# Un_AVR_V2_0.net
KiCad netlist of a schematic drawn in EAGLE
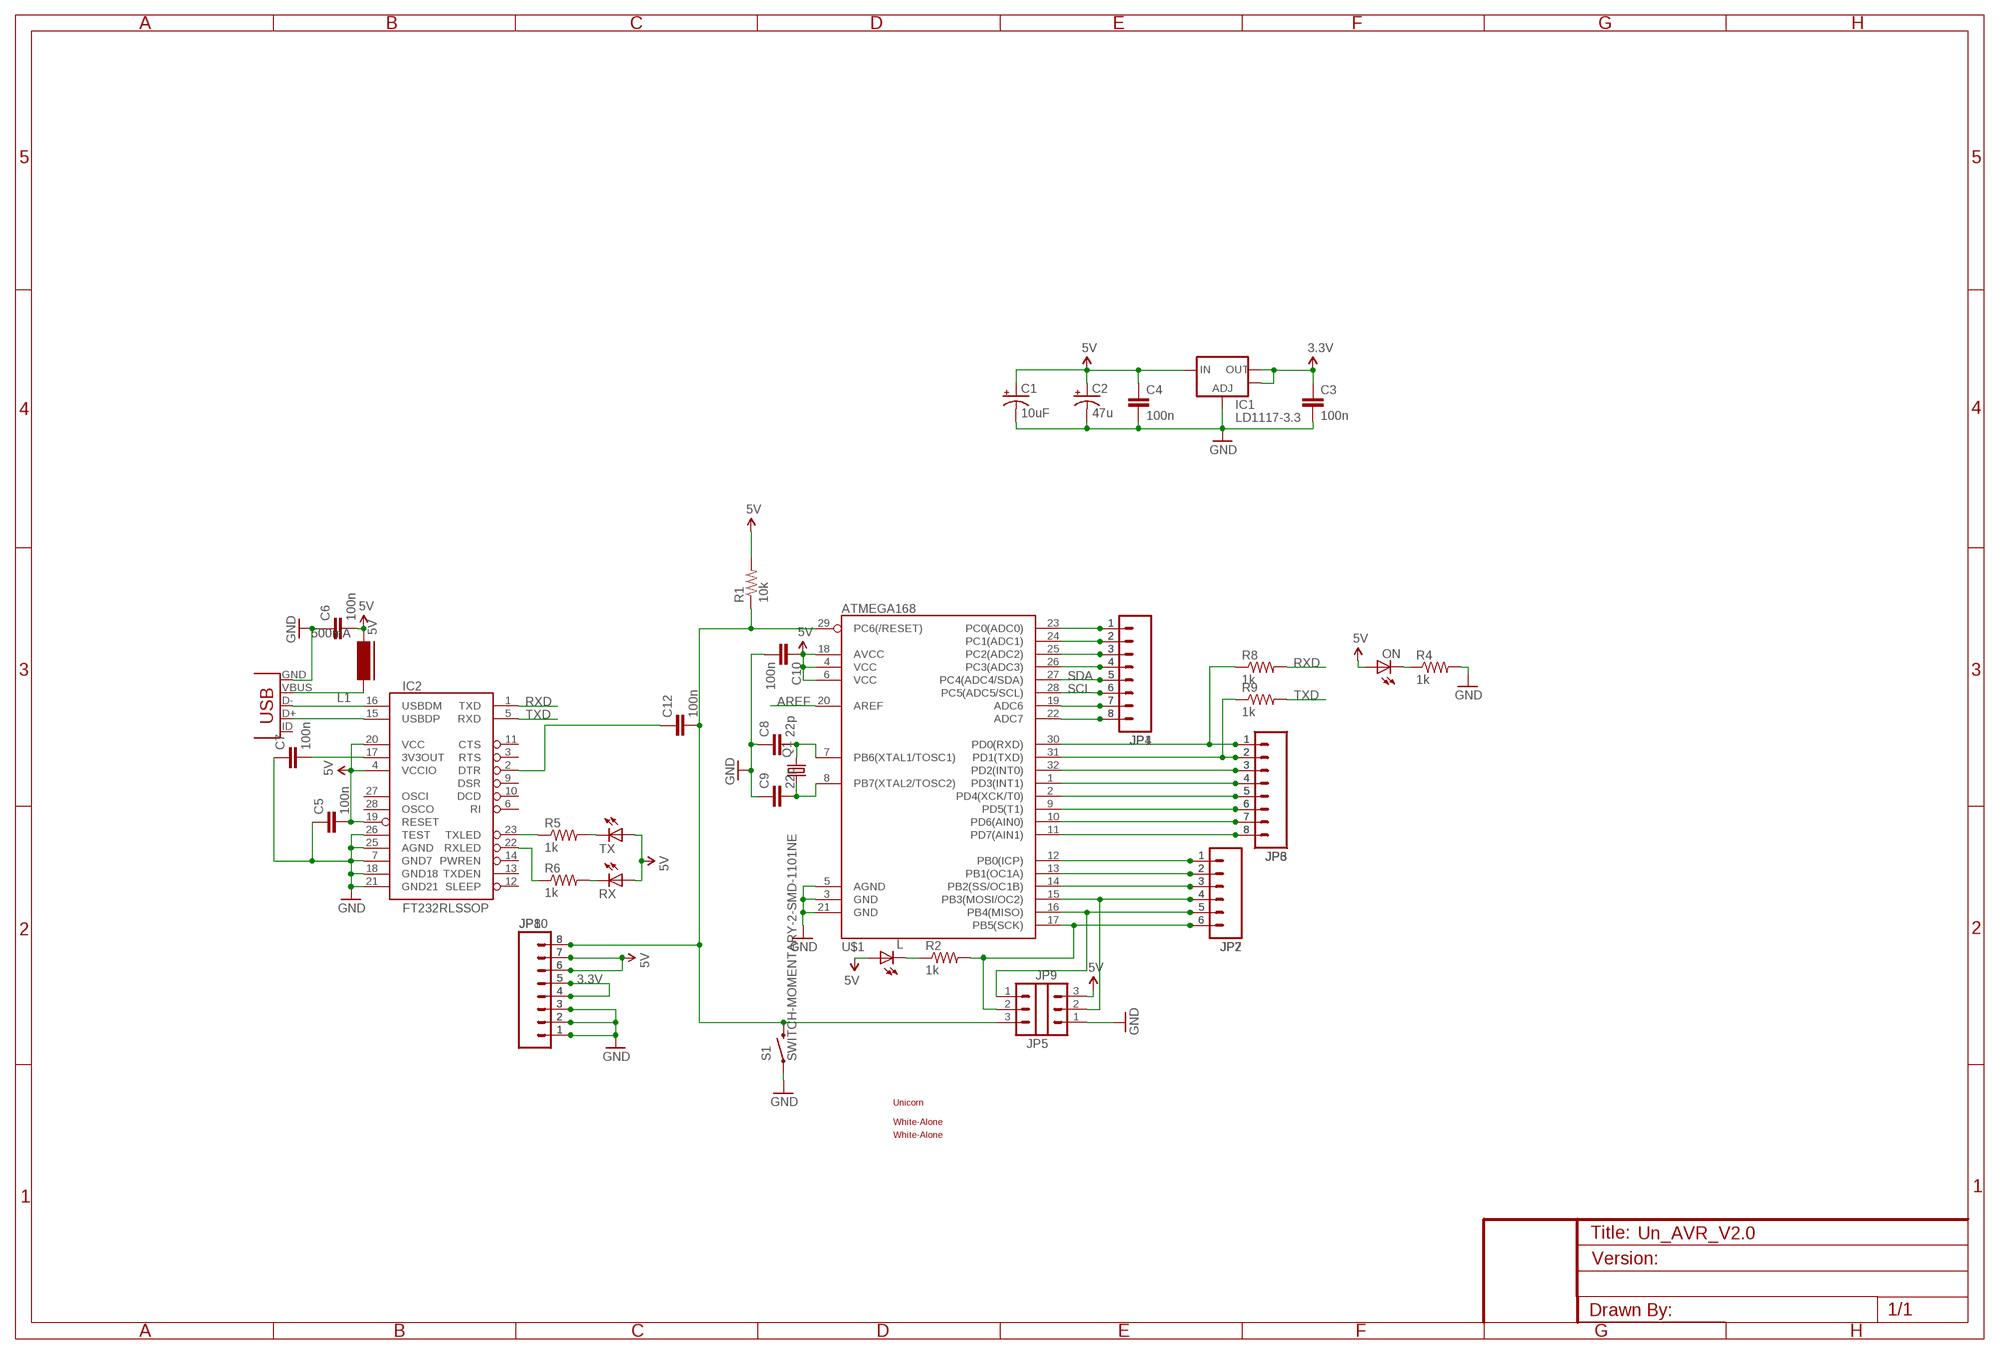
[diagram p0: schematic, sheet 1]

(export (version "E")
  (design (tool "Eeschema 10.0.6"))
  (components
    (comp (ref "C1")
      (value "10uF")
      (footprint "eagle-import:EIA3216")
      (libsource (lib "eagle-import") (part "CAP_POL1206"))
    )
    (comp (ref "C2")
      (value "47u")
      (footprint "eagle-import:PANASONIC_D")
      (libsource (lib "eagle-import") (part "CAP_POLD"))
    )
    (comp (ref "C3")
      (value "100n")
      (footprint "eagle-import:0603-CAP")
      (libsource (lib "eagle-import") (part "2SparkFun_CAP0603-CAP"))
    )
    (comp (ref "C4")
      (value "100n")
      (footprint "eagle-import:0603-CAP")
      (libsource (lib "eagle-import") (part "2SparkFun_CAP0603-CAP"))
    )
    (comp (ref "C5")
      (value "100n")
      (footprint "eagle-import:0603-CAP")
      (libsource (lib "eagle-import") (part "2SparkFun_CAP0603-CAP"))
    )
    (comp (ref "C6")
      (value "100n")
      (footprint "eagle-import:0603-CAP")
      (libsource (lib "eagle-import") (part "2SparkFun_CAP0603-CAP"))
    )
    (comp (ref "C7")
      (value "100n")
      (footprint "eagle-import:0603-CAP")
      (libsource (lib "eagle-import") (part "2SparkFun_CAP0603-CAP"))
    )
    (comp (ref "C8")
      (value "22p")
      (footprint "eagle-import:0603-CAP")
      (libsource (lib "eagle-import") (part "2SparkFun_CAP0603-CAP"))
    )
    (comp (ref "C9")
      (value "22p")
      (footprint "eagle-import:0603-CAP")
      (libsource (lib "eagle-import") (part "2SparkFun_CAP0603-CAP"))
    )
    (comp (ref "C10")
      (value "100n")
      (footprint "eagle-import:0603-CAP")
      (libsource (lib "eagle-import") (part "2SparkFun_CAP0603-CAP"))
    )
    (comp (ref "C12")
      (value "100n")
      (footprint "eagle-import:0603-CAP")
      (libsource (lib "eagle-import") (part "CAP0603-CAP"))
    )
    (comp (ref "IC1")
      (value "LD1117-3.3")
      (footprint "eagle-import:SOT223")
      (libsource (lib "eagle-import") (part "V_REG_LM1117SOT223"))
    )
    (comp (ref "IC2")
      (value "FT232RLSSOP")
      (footprint "eagle-import:SSOP28DB")
      (libsource (lib "eagle-import") (part "FT232RLSSOP"))
    )
    (comp (ref "JP1")
      (value "M081X08")
      (footprint "eagle-import:1X08")
      (libsource (lib "eagle-import") (part "M081X08"))
    )
    (comp (ref "JP2")
      (value "M06SIP")
      (footprint "eagle-import:1X06")
      (libsource (lib "eagle-import") (part "M06SIP"))
    )
    (comp (ref "JP3")
      (value "M08")
      (footprint "eagle-import:1X08")
      (libsource (lib "eagle-import") (part "M08"))
    )
    (comp (ref "JP4")
      (value "M081X08")
      (footprint "eagle-import:1X08")
      (libsource (lib "eagle-import") (part "M081X08"))
    )
    (comp (ref "JP5")
      (value "M03PTH")
      (footprint "eagle-import:1X03")
      (libsource (lib "eagle-import") (part "M03PTH"))
    )
    (comp (ref "JP6")
      (value "M08")
      (footprint "eagle-import:1X08")
      (libsource (lib "eagle-import") (part "M08"))
    )
    (comp (ref "JP7")
      (value "M06SIP")
      (footprint "eagle-import:1X06")
      (libsource (lib "eagle-import") (part "M06SIP"))
    )
    (comp (ref "JP8")
      (value "M08")
      (footprint "eagle-import:1X08")
      (libsource (lib "eagle-import") (part "M08"))
    )
    (comp (ref "JP9")
      (value "M03PTH")
      (footprint "eagle-import:1X03")
      (libsource (lib "eagle-import") (part "M03PTH"))
    )
    (comp (ref "JP10")
      (value "M08")
      (footprint "eagle-import:1X08")
      (libsource (lib "eagle-import") (part "M08"))
    )
    (comp (ref "L")
      (value "LED0805")
      (footprint "eagle-import:LED-0805")
      (libsource (lib "eagle-import") (part "LED0805"))
    )
    (comp (ref "L1")
      (value "500mA")
      (footprint "eagle-import:FB805")
      (libsource (lib "eagle-import") (part "FERRITE-0805"))
    )
    (comp (ref "ON")
      (value "LED0805")
      (footprint "eagle-import:LED-0805")
      (libsource (lib "eagle-import") (part "LED0805"))
    )
    (comp (ref "Q1")
      (value "CRYSTALHC49US")
      (footprint "eagle-import:HC49US")
      (libsource (lib "eagle-import") (part "CRYSTALHC49US"))
    )
    (comp (ref "R1")
      (value "10k")
      (footprint "eagle-import:0603-RES")
      (libsource (lib "eagle-import") (part "RESISTOR0603-RES"))
    )
    (comp (ref "R2")
      (value "1k")
      (footprint "eagle-import:0603-RES")
      (libsource (lib "eagle-import") (part "RESISTOR0603-RES"))
    )
    (comp (ref "R4")
      (value "1k")
      (footprint "eagle-import:0603-RES")
      (libsource (lib "eagle-import") (part "RESISTOR0603-RES"))
    )
    (comp (ref "R5")
      (value "1k")
      (footprint "eagle-import:0603-RES")
      (libsource (lib "eagle-import") (part "RESISTOR0603-RES"))
    )
    (comp (ref "R6")
      (value "1k")
      (footprint "eagle-import:0603-RES")
      (libsource (lib "eagle-import") (part "RESISTOR0603-RES"))
    )
    (comp (ref "R8")
      (value "1k")
      (footprint "eagle-import:0603-RES")
      (libsource (lib "eagle-import") (part "RESISTOR0603-RES"))
    )
    (comp (ref "R9")
      (value "1k")
      (footprint "eagle-import:0603-RES")
      (libsource (lib "eagle-import") (part "RESISTOR0603-RES"))
    )
    (comp (ref "RX")
      (value "LED0805")
      (footprint "eagle-import:LED-0805")
      (libsource (lib "eagle-import") (part "LED0805"))
    )
    (comp (ref "S1")
      (value "SWITCH-MOMENTARY-2-SMD-1101NE")
      (footprint "eagle-import:TACTILE-SWITCH-1101NE")
      (libsource (lib "eagle-import") (part "SWITCH-MOMENTARY-2-SMD-1101NE"))
    )
    (comp (ref "TX")
      (value "LED0805")
      (footprint "eagle-import:LED-0805")
      (libsource (lib "eagle-import") (part "LED0805"))
    )
    (comp (ref "U$1")
      (value "ATMEGA168")
      (footprint "eagle-import:TQFP32-08")
      (libsource (lib "eagle-import") (part "ATMEGA168"))
    )
    (comp (ref "U$4")
      (value "UNICORN_1")
      (footprint "eagle-import:UNICORN_1")
      (libsource (lib "eagle-import") (part "UNICORN_1"))
    )
    (comp (ref "U$13")
      (value "WHITE-ALONE_0")
      (footprint "eagle-import:WHITE-ALONE_0")
      (libsource (lib "eagle-import") (part "WHITE-ALONE_0"))
    )
    (comp (ref "U$14")
      (value "WHITE-ALONE_0")
      (footprint "eagle-import:WHITE-ALONE_0")
      (libsource (lib "eagle-import") (part "WHITE-ALONE_0"))
    )
    (comp (ref "U$16")
      (value "USB_5-SMD")
      (footprint "eagle-import:USB-MINIB")
      (libsource (lib "eagle-import") (part "USB_5-SMD"))
    )
  )
  (nets
    (net (code "1") (name "/AREF") (class "Default")
      (node (ref "U$1") (pin "20") (pinfunction "AREF_20") (pintype "bidirectional"))
    )
    (net (code "2") (name "/RXD") (class "Default")
      (node (ref "IC2") (pin "1") (pinfunction "TXD_1") (pintype "output"))
      (node (ref "R8") (pin "2") (pinfunction "2_2") (pintype "passive"))
    )
    (net (code "3") (name "/SCL") (class "Default")
      (node (ref "JP1") (pin "6") (pinfunction "6_6") (pintype "passive"))
      (node (ref "JP4") (pin "6") (pinfunction "6_6") (pintype "passive"))
      (node (ref "U$1") (pin "28") (pinfunction "PC5(ADC5/SCL)_28") (pintype "bidirectional"))
    )
    (net (code "4") (name "/SDA") (class "Default")
      (node (ref "JP1") (pin "5") (pinfunction "5_5") (pintype "passive"))
      (node (ref "JP4") (pin "5") (pinfunction "5_5") (pintype "passive"))
      (node (ref "U$1") (pin "27") (pinfunction "PC4(ADC4/SDA)_27") (pintype "bidirectional"))
    )
    (net (code "5") (name "/TXD") (class "Default")
      (node (ref "IC2") (pin "5") (pinfunction "RXD_5") (pintype "input"))
      (node (ref "R9") (pin "2") (pinfunction "2_2") (pintype "passive"))
    )
    (net (code "6") (name "3.3V") (class "Default")
      (node (ref "C3") (pin "1") (pinfunction "1_1") (pintype "passive"))
      (node (ref "IC1") (pin "2") (pinfunction "OUT_2") (pintype "output"))
      (node (ref "IC1") (pin "4") (pinfunction "OUT_4") (pintype "output"))
      (node (ref "JP10") (pin "4") (pinfunction "4_4") (pintype "passive"))
      (node (ref "JP10") (pin "5") (pinfunction "5_5") (pintype "passive"))
      (node (ref "JP8") (pin "4") (pinfunction "4_4") (pintype "passive"))
      (node (ref "JP8") (pin "5") (pinfunction "5_5") (pintype "passive"))
    )
    (net (code "7") (name "5V") (class "Default")
      (node (ref "C1") (pin "A") (pinfunction "+_A") (pintype "passive"))
      (node (ref "C10") (pin "1") (pinfunction "1_1") (pintype "passive"))
      (node (ref "C2") (pin "+") (pinfunction "+_+") (pintype "passive"))
      (node (ref "C4") (pin "1") (pinfunction "1_1") (pintype "passive"))
      (node (ref "C5") (pin "2") (pinfunction "2_2") (pintype "passive"))
      (node (ref "C6") (pin "2") (pinfunction "2_2") (pintype "passive"))
      (node (ref "IC1") (pin "3") (pinfunction "IN_3") (pintype "input"))
      (node (ref "IC2") (pin "19") (pinfunction "RESET_19") (pintype "input"))
      (node (ref "IC2") (pin "20") (pinfunction "VCC_20") (pintype "power_in"))
      (node (ref "IC2") (pin "4") (pinfunction "VCCIO_4") (pintype "power_in"))
      (node (ref "JP10") (pin "6") (pinfunction "6_6") (pintype "passive"))
      (node (ref "JP10") (pin "7") (pinfunction "7_7") (pintype "passive"))
      (node (ref "JP8") (pin "6") (pinfunction "6_6") (pintype "passive"))
      (node (ref "JP8") (pin "7") (pinfunction "7_7") (pintype "passive"))
      (node (ref "JP9") (pin "3") (pinfunction "3_3") (pintype "passive"))
      (node (ref "L") (pin "1") (pinfunction "A_1") (pintype "passive"))
      (node (ref "L1") (pin "2") (pinfunction "2_2") (pintype "passive"))
      (node (ref "ON") (pin "1") (pinfunction "A_1") (pintype "passive"))
      (node (ref "R1") (pin "2") (pinfunction "2_2") (pintype "passive"))
      (node (ref "RX") (pin "1") (pinfunction "A_1") (pintype "passive"))
      (node (ref "TX") (pin "1") (pinfunction "A_1") (pintype "passive"))
      (node (ref "U$1") (pin "18") (pinfunction "AVCC_18") (pintype "bidirectional"))
      (node (ref "U$1") (pin "4") (pinfunction "VCC_4") (pintype "bidirectional"))
      (node (ref "U$1") (pin "6") (pinfunction "VCC_6") (pintype "bidirectional"))
    )
    (net (code "8") (name "GND") (class "Default")
      (node (ref "C1") (pin "C") (pinfunction "-_C") (pintype "passive"))
      (node (ref "C10") (pin "2") (pinfunction "2_2") (pintype "passive"))
      (node (ref "C2") (pin "-") (pinfunction "-_-") (pintype "passive"))
      (node (ref "C3") (pin "2") (pinfunction "2_2") (pintype "passive"))
      (node (ref "C4") (pin "2") (pinfunction "2_2") (pintype "passive"))
      (node (ref "C5") (pin "1") (pinfunction "1_1") (pintype "passive"))
      (node (ref "C6") (pin "1") (pinfunction "1_1") (pintype "passive"))
      (node (ref "C7") (pin "1") (pinfunction "1_1") (pintype "passive"))
      (node (ref "C8") (pin "1") (pinfunction "1_1") (pintype "passive"))
      (node (ref "C9") (pin "1") (pinfunction "1_1") (pintype "passive"))
      (node (ref "IC1") (pin "1") (pinfunction "ADJ_1") (pintype "input"))
      (node (ref "IC2") (pin "18") (pinfunction "GND18_18") (pintype "power_in"))
      (node (ref "IC2") (pin "21") (pinfunction "GND21_21") (pintype "power_in"))
      (node (ref "IC2") (pin "25") (pinfunction "AGND_25") (pintype "power_in"))
      (node (ref "IC2") (pin "26") (pinfunction "TEST_26") (pintype "input"))
      (node (ref "IC2") (pin "7") (pinfunction "GND7_7") (pintype "power_in"))
      (node (ref "JP10") (pin "1") (pinfunction "1_1") (pintype "passive"))
      (node (ref "JP10") (pin "2") (pinfunction "2_2") (pintype "passive"))
      (node (ref "JP10") (pin "3") (pinfunction "3_3") (pintype "passive"))
      (node (ref "JP8") (pin "1") (pinfunction "1_1") (pintype "passive"))
      (node (ref "JP8") (pin "2") (pinfunction "2_2") (pintype "passive"))
      (node (ref "JP8") (pin "3") (pinfunction "3_3") (pintype "passive"))
      (node (ref "JP9") (pin "1") (pinfunction "1_1") (pintype "passive"))
      (node (ref "R4") (pin "2") (pinfunction "2_2") (pintype "passive"))
      (node (ref "S1") (pin "P$1") (pinfunction "1_P$1") (pintype "passive"))
      (node (ref "U$1") (pin "21") (pinfunction "GND_21") (pintype "bidirectional"))
      (node (ref "U$1") (pin "3") (pinfunction "GND_3") (pintype "bidirectional"))
      (node (ref "U$1") (pin "5") (pinfunction "AGND_5") (pintype "bidirectional"))
      (node (ref "U$16") (pin "GND") (pinfunction "GND_GND") (pintype "bidirectional"))
    )
    (net (code "9") (name "Net-(IC2-3V3OUT)") (class "Default")
      (node (ref "C7") (pin "2") (pinfunction "2_2") (pintype "passive"))
      (node (ref "IC2") (pin "17") (pinfunction "3V3OUT_17") (pintype "output"))
    )
    (net (code "10") (name "Net-(IC2-DTR)") (class "Default")
      (node (ref "C12") (pin "1") (pinfunction "1_1") (pintype "passive"))
      (node (ref "IC2") (pin "2") (pinfunction "DTR_2") (pintype "output"))
    )
    (net (code "11") (name "Net-(IC2-RXLED)") (class "Default")
      (node (ref "IC2") (pin "22") (pinfunction "RXLED_22") (pintype "input"))
      (node (ref "R6") (pin "1") (pinfunction "1_1") (pintype "passive"))
    )
    (net (code "12") (name "Net-(IC2-TXLED)") (class "Default")
      (node (ref "IC2") (pin "23") (pinfunction "TXLED_23") (pintype "input"))
      (node (ref "R5") (pin "1") (pinfunction "1_1") (pintype "passive"))
    )
    (net (code "13") (name "Net-(IC2-USBDM)") (class "Default")
      (node (ref "IC2") (pin "16") (pinfunction "USBDM_16") (pintype "bidirectional"))
      (node (ref "U$16") (pin "D-") (pinfunction "D-_D-") (pintype "bidirectional"))
    )
    (net (code "14") (name "Net-(IC2-USBDP)") (class "Default")
      (node (ref "IC2") (pin "15") (pinfunction "USBDP_15") (pintype "bidirectional"))
      (node (ref "U$16") (pin "D+") (pinfunction "D+_D+") (pintype "bidirectional"))
    )
    (net (code "15") (name "Net-(L-C)") (class "Default")
      (node (ref "L") (pin "2") (pinfunction "C_2") (pintype "passive"))
      (node (ref "R2") (pin "1") (pinfunction "1_1") (pintype "passive"))
    )
    (net (code "16") (name "Net-(L1-Pad1)") (class "Default")
      (node (ref "L1") (pin "1") (pinfunction "1_1") (pintype "passive"))
      (node (ref "U$16") (pin "VBUS") (pinfunction "VBUS_VBUS") (pintype "bidirectional"))
    )
    (net (code "17") (name "Net-(ON-C)") (class "Default")
      (node (ref "ON") (pin "2") (pinfunction "C_2") (pintype "passive"))
      (node (ref "R4") (pin "1") (pinfunction "1_1") (pintype "passive"))
    )
    (net (code "18") (name "Net-(RX-C)") (class "Default")
      (node (ref "R6") (pin "2") (pinfunction "2_2") (pintype "passive"))
      (node (ref "RX") (pin "2") (pinfunction "C_2") (pintype "passive"))
    )
    (net (code "19") (name "Net-(S1-2)") (class "Default")
      (node (ref "C12") (pin "2") (pinfunction "2_2") (pintype "passive"))
      (node (ref "JP10") (pin "8") (pinfunction "8_8") (pintype "passive"))
      (node (ref "JP5") (pin "3") (pinfunction "3_3") (pintype "passive"))
      (node (ref "JP8") (pin "8") (pinfunction "8_8") (pintype "passive"))
      (node (ref "R1") (pin "1") (pinfunction "1_1") (pintype "passive"))
      (node (ref "S1") (pin "P$2") (pinfunction "2_P$2") (pintype "passive"))
      (node (ref "U$1") (pin "29") (pinfunction "PC6(/RESET)_29") (pintype "bidirectional"))
    )
    (net (code "20") (name "Net-(TX-C)") (class "Default")
      (node (ref "R5") (pin "2") (pinfunction "2_2") (pintype "passive"))
      (node (ref "TX") (pin "2") (pinfunction "C_2") (pintype "passive"))
    )
    (net (code "21") (name "Net-(U$1-ADC6)") (class "Default")
      (node (ref "JP1") (pin "7") (pinfunction "7_7") (pintype "passive"))
      (node (ref "JP4") (pin "7") (pinfunction "7_7") (pintype "passive"))
      (node (ref "U$1") (pin "19") (pinfunction "ADC6_19") (pintype "bidirectional"))
    )
    (net (code "22") (name "Net-(U$1-ADC7)") (class "Default")
      (node (ref "JP1") (pin "8") (pinfunction "8_8") (pintype "passive"))
      (node (ref "JP4") (pin "8") (pinfunction "8_8") (pintype "passive"))
      (node (ref "U$1") (pin "22") (pinfunction "ADC7_22") (pintype "bidirectional"))
    )
    (net (code "23") (name "Net-(U$1-PB0(ICP))") (class "Default")
      (node (ref "JP2") (pin "1") (pinfunction "1_1") (pintype "passive"))
      (node (ref "JP7") (pin "1") (pinfunction "1_1") (pintype "passive"))
      (node (ref "U$1") (pin "12") (pinfunction "PB0(ICP)_12") (pintype "bidirectional"))
    )
    (net (code "24") (name "Net-(U$1-PB1(OC1A))") (class "Default")
      (node (ref "JP2") (pin "2") (pinfunction "2_2") (pintype "passive"))
      (node (ref "JP7") (pin "2") (pinfunction "2_2") (pintype "passive"))
      (node (ref "U$1") (pin "13") (pinfunction "PB1(OC1A)_13") (pintype "bidirectional"))
    )
    (net (code "25") (name "Net-(U$1-PB2(SS{slash}OC1B))") (class "Default")
      (node (ref "JP2") (pin "3") (pinfunction "3_3") (pintype "passive"))
      (node (ref "JP7") (pin "3") (pinfunction "3_3") (pintype "passive"))
      (node (ref "U$1") (pin "14") (pinfunction "PB2(SS/OC1B)_14") (pintype "bidirectional"))
    )
    (net (code "26") (name "Net-(U$1-PB3(MOSI{slash}OC2))") (class "Default")
      (node (ref "JP2") (pin "4") (pinfunction "4_4") (pintype "passive"))
      (node (ref "JP7") (pin "4") (pinfunction "4_4") (pintype "passive"))
      (node (ref "JP9") (pin "2") (pinfunction "2_2") (pintype "passive"))
      (node (ref "U$1") (pin "15") (pinfunction "PB3(MOSI/OC2)_15") (pintype "bidirectional"))
    )
    (net (code "27") (name "Net-(U$1-PB4(MISO))") (class "Default")
      (node (ref "JP2") (pin "5") (pinfunction "5_5") (pintype "passive"))
      (node (ref "JP5") (pin "1") (pinfunction "1_1") (pintype "passive"))
      (node (ref "JP7") (pin "5") (pinfunction "5_5") (pintype "passive"))
      (node (ref "U$1") (pin "16") (pinfunction "PB4(MISO)_16") (pintype "bidirectional"))
    )
    (net (code "28") (name "Net-(U$1-PB5(SCK))") (class "Default")
      (node (ref "JP2") (pin "6") (pinfunction "6_6") (pintype "passive"))
      (node (ref "JP5") (pin "2") (pinfunction "2_2") (pintype "passive"))
      (node (ref "JP7") (pin "6") (pinfunction "6_6") (pintype "passive"))
      (node (ref "R2") (pin "2") (pinfunction "2_2") (pintype "passive"))
      (node (ref "U$1") (pin "17") (pinfunction "PB5(SCK)_17") (pintype "bidirectional"))
    )
    (net (code "29") (name "Net-(U$1-PB6(XTAL1{slash}TOSC1))") (class "Default")
      (node (ref "C8") (pin "2") (pinfunction "2_2") (pintype "passive"))
      (node (ref "Q1") (pin "2") (pinfunction "2_2") (pintype "passive"))
      (node (ref "U$1") (pin "7") (pinfunction "PB6(XTAL1/TOSC1)_7") (pintype "bidirectional"))
    )
    (net (code "30") (name "Net-(U$1-PB7(XTAL2{slash}TOSC2))") (class "Default")
      (node (ref "C9") (pin "2") (pinfunction "2_2") (pintype "passive"))
      (node (ref "Q1") (pin "1") (pinfunction "1_1") (pintype "passive"))
      (node (ref "U$1") (pin "8") (pinfunction "PB7(XTAL2/TOSC2)_8") (pintype "bidirectional"))
    )
    (net (code "31") (name "Net-(U$1-PC0(ADC0))") (class "Default")
      (node (ref "JP1") (pin "1") (pinfunction "1_1") (pintype "passive"))
      (node (ref "JP4") (pin "1") (pinfunction "1_1") (pintype "passive"))
      (node (ref "U$1") (pin "23") (pinfunction "PC0(ADC0)_23") (pintype "bidirectional"))
    )
    (net (code "32") (name "Net-(U$1-PC1(ADC1))") (class "Default")
      (node (ref "JP1") (pin "2") (pinfunction "2_2") (pintype "passive"))
      (node (ref "JP4") (pin "2") (pinfunction "2_2") (pintype "passive"))
      (node (ref "U$1") (pin "24") (pinfunction "PC1(ADC1)_24") (pintype "bidirectional"))
    )
    (net (code "33") (name "Net-(U$1-PC2(ADC2))") (class "Default")
      (node (ref "JP1") (pin "3") (pinfunction "3_3") (pintype "passive"))
      (node (ref "JP4") (pin "3") (pinfunction "3_3") (pintype "passive"))
      (node (ref "U$1") (pin "25") (pinfunction "PC2(ADC2)_25") (pintype "bidirectional"))
    )
    (net (code "34") (name "Net-(U$1-PC3(ADC3))") (class "Default")
      (node (ref "JP1") (pin "4") (pinfunction "4_4") (pintype "passive"))
      (node (ref "JP4") (pin "4") (pinfunction "4_4") (pintype "passive"))
      (node (ref "U$1") (pin "26") (pinfunction "PC3(ADC3)_26") (pintype "bidirectional"))
    )
    (net (code "35") (name "Net-(U$1-PD0(RXD))") (class "Default")
      (node (ref "JP3") (pin "1") (pinfunction "1_1") (pintype "passive"))
      (node (ref "JP6") (pin "1") (pinfunction "1_1") (pintype "passive"))
      (node (ref "R8") (pin "1") (pinfunction "1_1") (pintype "passive"))
      (node (ref "U$1") (pin "30") (pinfunction "PD0(RXD)_30") (pintype "bidirectional"))
    )
    (net (code "36") (name "Net-(U$1-PD1(TXD))") (class "Default")
      (node (ref "JP3") (pin "2") (pinfunction "2_2") (pintype "passive"))
      (node (ref "JP6") (pin "2") (pinfunction "2_2") (pintype "passive"))
      (node (ref "R9") (pin "1") (pinfunction "1_1") (pintype "passive"))
      (node (ref "U$1") (pin "31") (pinfunction "PD1(TXD)_31") (pintype "bidirectional"))
    )
    (net (code "37") (name "Net-(U$1-PD2(INT0))") (class "Default")
      (node (ref "JP3") (pin "3") (pinfunction "3_3") (pintype "passive"))
      (node (ref "JP6") (pin "3") (pinfunction "3_3") (pintype "passive"))
      (node (ref "U$1") (pin "32") (pinfunction "PD2(INT0)_32") (pintype "bidirectional"))
    )
    (net (code "38") (name "Net-(U$1-PD3(INT1))") (class "Default")
      (node (ref "JP3") (pin "4") (pinfunction "4_4") (pintype "passive"))
      (node (ref "JP6") (pin "4") (pinfunction "4_4") (pintype "passive"))
      (node (ref "U$1") (pin "1") (pinfunction "PD3(INT1)_1") (pintype "bidirectional"))
    )
    (net (code "39") (name "Net-(U$1-PD4(XCK{slash}T0))") (class "Default")
      (node (ref "JP3") (pin "5") (pinfunction "5_5") (pintype "passive"))
      (node (ref "JP6") (pin "5") (pinfunction "5_5") (pintype "passive"))
      (node (ref "U$1") (pin "2") (pinfunction "PD4(XCK/T0)_2") (pintype "bidirectional"))
    )
    (net (code "40") (name "Net-(U$1-PD5(T1))") (class "Default")
      (node (ref "JP3") (pin "6") (pinfunction "6_6") (pintype "passive"))
      (node (ref "JP6") (pin "6") (pinfunction "6_6") (pintype "passive"))
      (node (ref "U$1") (pin "9") (pinfunction "PD5(T1)_9") (pintype "bidirectional"))
    )
    (net (code "41") (name "Net-(U$1-PD6(AIN0))") (class "Default")
      (node (ref "JP3") (pin "7") (pinfunction "7_7") (pintype "passive"))
      (node (ref "JP6") (pin "7") (pinfunction "7_7") (pintype "passive"))
      (node (ref "U$1") (pin "10") (pinfunction "PD6(AIN0)_10") (pintype "bidirectional"))
    )
    (net (code "42") (name "Net-(U$1-PD7(AIN1))") (class "Default")
      (node (ref "JP3") (pin "8") (pinfunction "8_8") (pintype "passive"))
      (node (ref "JP6") (pin "8") (pinfunction "8_8") (pintype "passive"))
      (node (ref "U$1") (pin "11") (pinfunction "PD7(AIN1)_11") (pintype "bidirectional"))
    )
    (net (code "43") (name "unconnected-(IC2-CTS-Pad11)") (class "Default")
      (node (ref "IC2") (pin "11") (pinfunction "CTS_11") (pintype "input"))
    )
    (net (code "44") (name "unconnected-(IC2-DCD-Pad10)") (class "Default")
      (node (ref "IC2") (pin "10") (pinfunction "DCD_10") (pintype "input"))
    )
    (net (code "45") (name "unconnected-(IC2-DSR-Pad9)") (class "Default")
      (node (ref "IC2") (pin "9") (pinfunction "DSR_9") (pintype "input"))
    )
    (net (code "46") (name "unconnected-(IC2-OSCI-Pad27)") (class "Default")
      (node (ref "IC2") (pin "27") (pinfunction "OSCI_27") (pintype "input"))
    )
    (net (code "47") (name "unconnected-(IC2-OSCO-Pad28)") (class "Default")
      (node (ref "IC2") (pin "28") (pinfunction "OSCO_28") (pintype "output"))
    )
    (net (code "48") (name "unconnected-(IC2-PWREN-Pad14)") (class "Default")
      (node (ref "IC2") (pin "14") (pinfunction "PWREN_14") (pintype "input"))
    )
    (net (code "49") (name "unconnected-(IC2-RI-Pad6)") (class "Default")
      (node (ref "IC2") (pin "6") (pinfunction "RI_6") (pintype "input"))
    )
    (net (code "50") (name "unconnected-(IC2-RTS-Pad3)") (class "Default")
      (node (ref "IC2") (pin "3") (pinfunction "RTS_3") (pintype "output"))
    )
    (net (code "51") (name "unconnected-(IC2-SLEEP-Pad12)") (class "Default")
      (node (ref "IC2") (pin "12") (pinfunction "SLEEP_12") (pintype "input"))
    )
    (net (code "52") (name "unconnected-(IC2-TXDEN-Pad13)") (class "Default")
      (node (ref "IC2") (pin "13") (pinfunction "TXDEN_13") (pintype "input"))
    )
    (net (code "53") (name "unconnected-(U$16-USBID-PadID)") (class "Default")
      (node (ref "U$16") (pin "ID") (pinfunction "USBID_ID") (pintype "bidirectional"))
    )
  )
)
